# Multimodal_v4.net
KiCad netlist of a schematic drawn in EAGLE
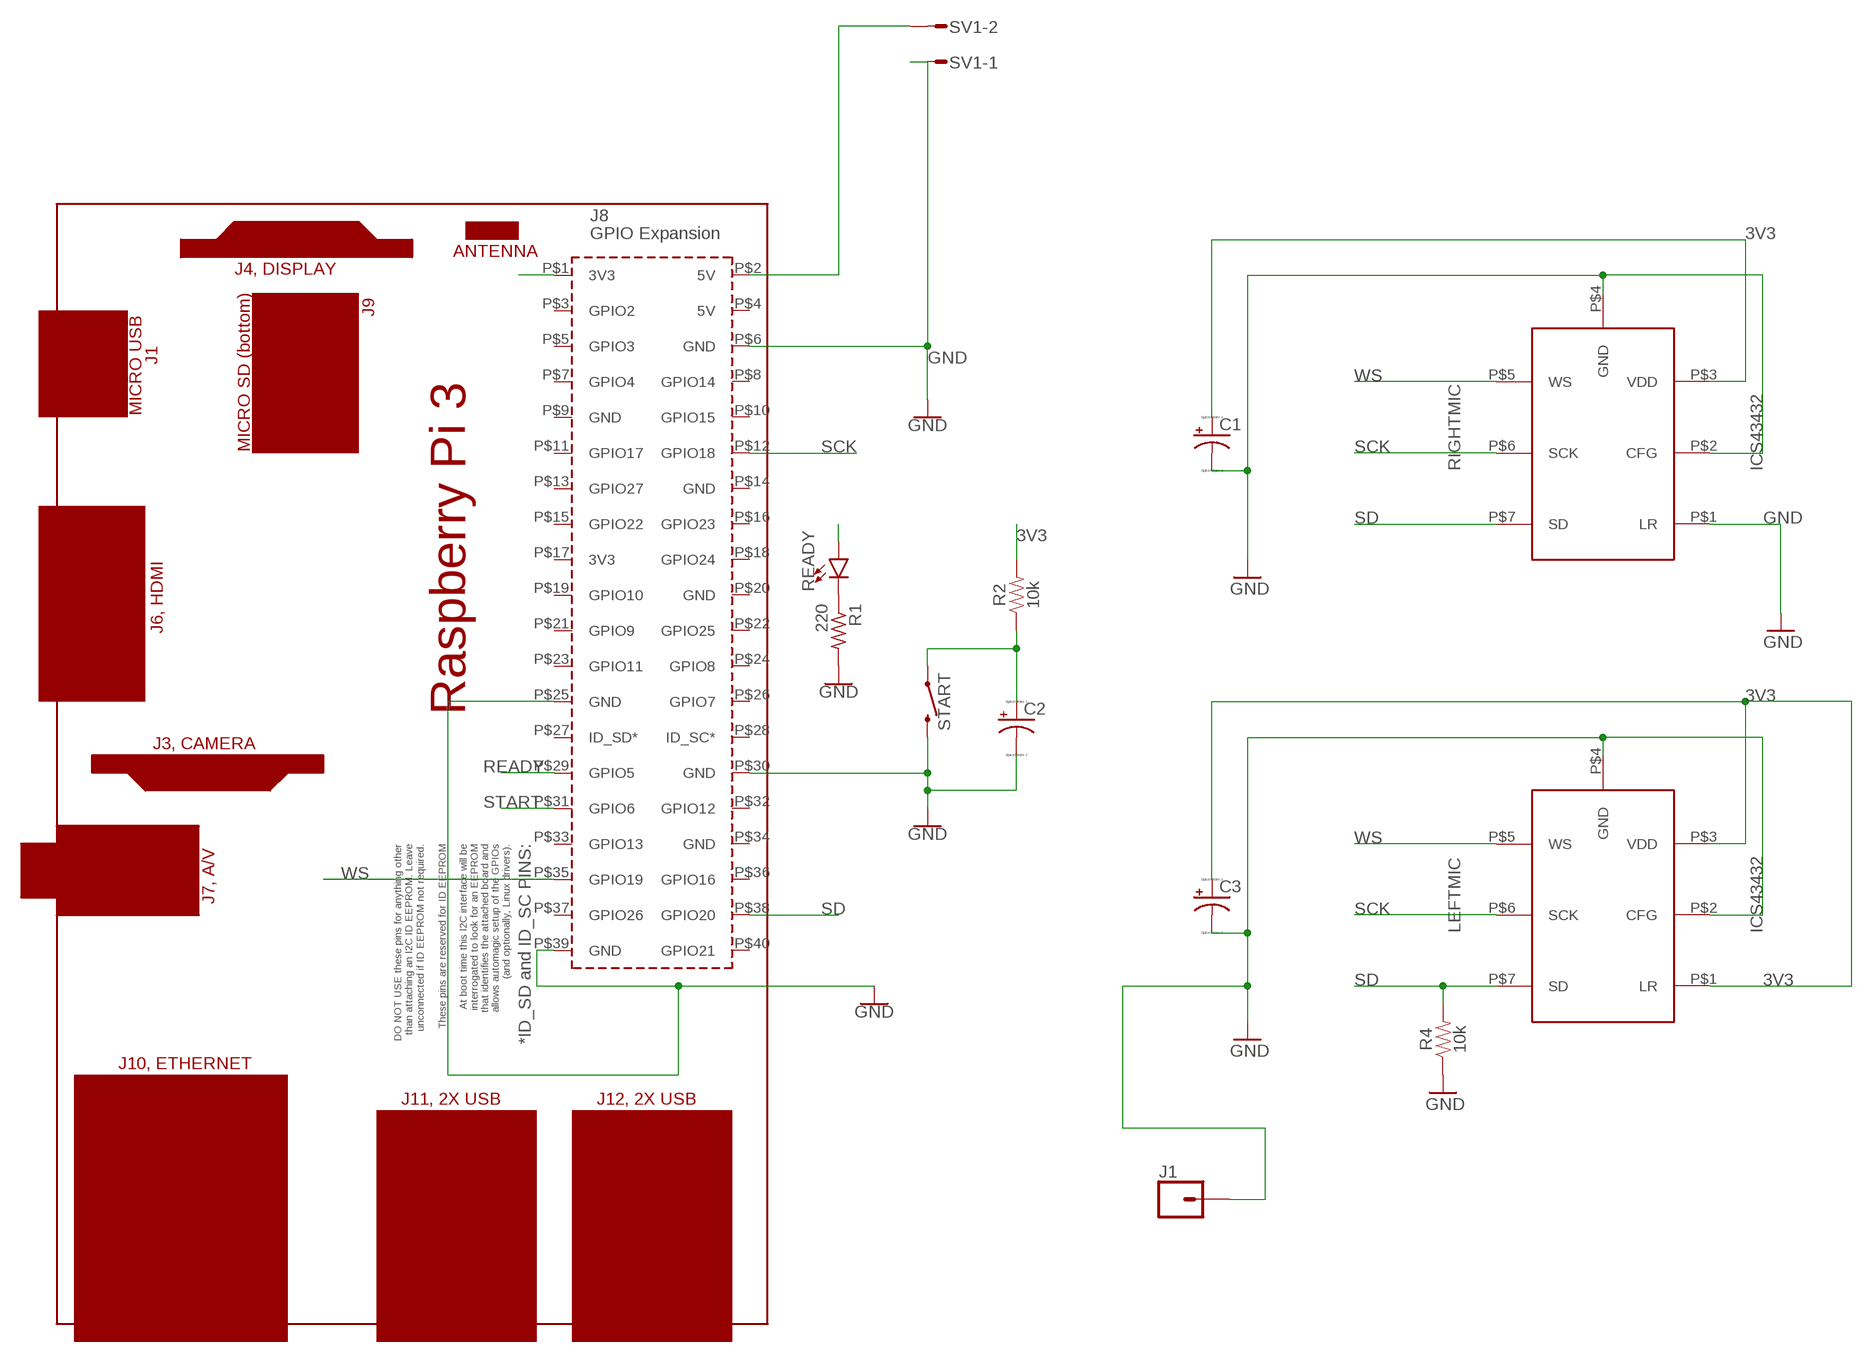
[diagram p0: schematic, sheet 1]

(export (version "E")
  (design (tool "Eeschema 10.0.6"))
  (components
    (comp (ref "C1")
      (value "CPOL-USE2.5-5")
      (footprint "eagle-import:E2,5-5")
      (libsource (lib "eagle-import") (part "CPOL-USE2.5-5"))
    )
    (comp (ref "C2")
      (value "CPOL-USE2.5-5")
      (footprint "eagle-import:E2,5-5")
      (libsource (lib "eagle-import") (part "CPOL-USE2.5-5"))
    )
    (comp (ref "C3")
      (value "CPOL-USE2.5-5")
      (footprint "eagle-import:E2,5-5")
      (libsource (lib "eagle-import") (part "CPOL-USE2.5-5"))
    )
    (comp (ref "J1")
      (value "CONN_01")
      (footprint "eagle-import:1X01")
      (libsource (lib "eagle-import") (part "CONN_01"))
    )
    (comp (ref "LEFTMIC")
      (value "ICS43432")
      (footprint "eagle-import:ICS43432")
      (libsource (lib "eagle-import") (part "ICS43432"))
    )
    (comp (ref "PCB1")
      (value "RPI3_40_PIN")
      (footprint "eagle-import:40_PIN")
      (libsource (lib "eagle-import") (part "RPI3_40_PIN"))
    )
    (comp (ref "R1")
      (value "220")
      (footprint "eagle-import:0207_7")
      (libsource (lib "eagle-import") (part "R-US_0207/7"))
    )
    (comp (ref "R2")
      (value "10k")
      (footprint "eagle-import:AXIAL-0.3-KIT")
      (libsource (lib "eagle-import") (part "10KOHM-HORIZ_KIT-1/4W-5%"))
    )
    (comp (ref "R4")
      (value "10k")
      (footprint "eagle-import:AXIAL-0.3-KIT")
      (libsource (lib "eagle-import") (part "10KOHM-HORIZ_KIT-1/4W-5%"))
    )
    (comp (ref "READY")
      (value "LED3MM")
      (footprint "eagle-import:LED_3MM")
      (libsource (lib "eagle-import") (part "LED3MM"))
    )
    (comp (ref "RIGHTMIC")
      (value "ICS43432")
      (footprint "eagle-import:ICS43432")
      (libsource (lib "eagle-import") (part "ICS43432"))
    )
    (comp (ref "START")
      (value "MOMENTARY-SWITCH-SPST-PTH-6.0MM")
      (footprint "eagle-import:TACTILE_SWITCH_PTH_6.0MM")
      (libsource (lib "eagle-import") (part "MOMENTARY-SWITCH-SPST-PTH-6.0MM"))
    )
    (comp (ref "SV1")
      (value "L02P")
      (footprint "eagle-import:L02P")
      (libsource (lib "eagle-import") (part "L02P"))
    )
  )
  (nets
    (net (code "1") (name "/3V3") (class "Default")
      (node (ref "C1") (pin "+") (pinfunction "+_+") (pintype "passive"))
      (node (ref "C3") (pin "+") (pinfunction "+_+") (pintype "passive"))
      (node (ref "LEFTMIC") (pin "P$1") (pinfunction "LR_P$1") (pintype "bidirectional"))
      (node (ref "LEFTMIC") (pin "P$3") (pinfunction "VDD_P$3") (pintype "bidirectional"))
      (node (ref "PCB1") (pin "P$1") (pinfunction "3V3_P$1") (pintype "bidirectional"))
      (node (ref "R2") (pin "P$2") (pinfunction "2_P$2") (pintype "passive"))
      (node (ref "RIGHTMIC") (pin "P$3") (pinfunction "VDD_P$3") (pintype "bidirectional"))
    )
    (net (code "2") (name "/READY") (class "Default")
      (node (ref "PCB1") (pin "P$29") (pinfunction "GPIO5_P$29") (pintype "bidirectional"))
      (node (ref "READY") (pin "A") (pinfunction "A_A") (pintype "passive"))
    )
    (net (code "3") (name "/SCK") (class "Default")
      (node (ref "LEFTMIC") (pin "P$6") (pinfunction "SCK_P$6") (pintype "bidirectional"))
      (node (ref "PCB1") (pin "P$12") (pinfunction "GPIO18_P$12") (pintype "bidirectional"))
      (node (ref "RIGHTMIC") (pin "P$6") (pinfunction "SCK_P$6") (pintype "bidirectional"))
    )
    (net (code "4") (name "/SD") (class "Default")
      (node (ref "LEFTMIC") (pin "P$7") (pinfunction "SD_P$7") (pintype "bidirectional"))
      (node (ref "PCB1") (pin "P$38") (pinfunction "GPIO20_P$38") (pintype "bidirectional"))
      (node (ref "R4") (pin "P$2") (pinfunction "2_P$2") (pintype "passive"))
      (node (ref "RIGHTMIC") (pin "P$7") (pinfunction "SD_P$7") (pintype "bidirectional"))
    )
    (net (code "5") (name "/START") (class "Default")
      (node (ref "C2") (pin "+") (pinfunction "+_+") (pintype "passive"))
      (node (ref "PCB1") (pin "P$31") (pinfunction "GPIO6_P$31") (pintype "bidirectional"))
      (node (ref "R2") (pin "P$1") (pinfunction "1_P$1") (pintype "passive"))
      (node (ref "START") (pin "1") (pinfunction "1_1") (pintype "passive"))
    )
    (net (code "6") (name "/WS") (class "Default")
      (node (ref "LEFTMIC") (pin "P$5") (pinfunction "WS_P$5") (pintype "bidirectional"))
      (node (ref "PCB1") (pin "P$35") (pinfunction "GPIO19_P$35") (pintype "bidirectional"))
      (node (ref "RIGHTMIC") (pin "P$5") (pinfunction "WS_P$5") (pintype "bidirectional"))
    )
    (net (code "7") (name "GND") (class "Default")
      (node (ref "C1") (pin "-") (pinfunction "-_-") (pintype "passive"))
      (node (ref "C2") (pin "-") (pinfunction "-_-") (pintype "passive"))
      (node (ref "C3") (pin "-") (pinfunction "-_-") (pintype "passive"))
      (node (ref "J1") (pin "1") (pinfunction "1_1") (pintype "passive"))
      (node (ref "LEFTMIC") (pin "P$2") (pinfunction "CFG_P$2") (pintype "bidirectional"))
      (node (ref "LEFTMIC") (pin "P$4") (pinfunction "GND_P$4") (pintype "bidirectional"))
      (node (ref "PCB1") (pin "P$25") (pinfunction "GND_P$25") (pintype "bidirectional"))
      (node (ref "PCB1") (pin "P$30") (pinfunction "GND_P$30") (pintype "bidirectional"))
      (node (ref "PCB1") (pin "P$39") (pinfunction "GND_P$39") (pintype "bidirectional"))
      (node (ref "PCB1") (pin "P$6") (pinfunction "GND_P$6") (pintype "bidirectional"))
      (node (ref "R1") (pin "2") (pinfunction "2_2") (pintype "passive"))
      (node (ref "R4") (pin "P$1") (pinfunction "1_P$1") (pintype "passive"))
      (node (ref "RIGHTMIC") (pin "P$1") (pinfunction "LR_P$1") (pintype "bidirectional"))
      (node (ref "RIGHTMIC") (pin "P$2") (pinfunction "CFG_P$2") (pintype "bidirectional"))
      (node (ref "RIGHTMIC") (pin "P$4") (pinfunction "GND_P$4") (pintype "bidirectional"))
      (node (ref "START") (pin "3") (pinfunction "2_3") (pintype "passive"))
      (node (ref "SV1") (pin "1") (pinfunction "S_1") (pintype "passive"))
    )
    (net (code "8") (name "Net-(READY-C)") (class "Default")
      (node (ref "R1") (pin "1") (pinfunction "1_1") (pintype "passive"))
      (node (ref "READY") (pin "K") (pinfunction "C_K") (pintype "passive"))
    )
    (net (code "9") (name "Net-(SV1B-S)") (class "Default")
      (node (ref "PCB1") (pin "P$2") (pinfunction "5V_P$2") (pintype "bidirectional"))
      (node (ref "SV1") (pin "2") (pinfunction "S_2") (pintype "passive"))
    )
    (net (code "10") (name "unconnected-(PCB1-3V3-PadP$17)") (class "Default")
      (node (ref "PCB1") (pin "P$17") (pinfunction "3V3_P$17") (pintype "bidirectional"))
    )
    (net (code "11") (name "unconnected-(PCB1-5V-PadP$4)") (class "Default")
      (node (ref "PCB1") (pin "P$4") (pinfunction "5V_P$4") (pintype "bidirectional"))
    )
    (net (code "12") (name "unconnected-(PCB1-GND-PadP$9)") (class "Default")
      (node (ref "PCB1") (pin "P$9") (pinfunction "GND_P$9") (pintype "bidirectional"))
    )
    (net (code "13") (name "unconnected-(PCB1-GND-PadP$14)") (class "Default")
      (node (ref "PCB1") (pin "P$14") (pinfunction "GND_P$14") (pintype "bidirectional"))
    )
    (net (code "14") (name "unconnected-(PCB1-GND-PadP$20)") (class "Default")
      (node (ref "PCB1") (pin "P$20") (pinfunction "GND_P$20") (pintype "bidirectional"))
    )
    (net (code "15") (name "unconnected-(PCB1-GND-PadP$34)") (class "Default")
      (node (ref "PCB1") (pin "P$34") (pinfunction "GND_P$34") (pintype "bidirectional"))
    )
    (net (code "16") (name "unconnected-(PCB1-GPIO2-PadP$3)") (class "Default")
      (node (ref "PCB1") (pin "P$3") (pinfunction "GPIO2_P$3") (pintype "bidirectional"))
    )
    (net (code "17") (name "unconnected-(PCB1-GPIO3-PadP$5)") (class "Default")
      (node (ref "PCB1") (pin "P$5") (pinfunction "GPIO3_P$5") (pintype "bidirectional"))
    )
    (net (code "18") (name "unconnected-(PCB1-GPIO4-PadP$7)") (class "Default")
      (node (ref "PCB1") (pin "P$7") (pinfunction "GPIO4_P$7") (pintype "bidirectional"))
    )
    (net (code "19") (name "unconnected-(PCB1-GPIO7-PadP$26)") (class "Default")
      (node (ref "PCB1") (pin "P$26") (pinfunction "GPIO7_P$26") (pintype "bidirectional"))
    )
    (net (code "20") (name "unconnected-(PCB1-GPIO8-PadP$24)") (class "Default")
      (node (ref "PCB1") (pin "P$24") (pinfunction "GPIO8_P$24") (pintype "bidirectional"))
    )
    (net (code "21") (name "unconnected-(PCB1-GPIO9-PadP$21)") (class "Default")
      (node (ref "PCB1") (pin "P$21") (pinfunction "GPIO9_P$21") (pintype "bidirectional"))
    )
    (net (code "22") (name "unconnected-(PCB1-GPIO10-PadP$19)") (class "Default")
      (node (ref "PCB1") (pin "P$19") (pinfunction "GPIO10_P$19") (pintype "bidirectional"))
    )
    (net (code "23") (name "unconnected-(PCB1-GPIO11-PadP$23)") (class "Default")
      (node (ref "PCB1") (pin "P$23") (pinfunction "GPIO11_P$23") (pintype "bidirectional"))
    )
    (net (code "24") (name "unconnected-(PCB1-GPIO12-PadP$32)") (class "Default")
      (node (ref "PCB1") (pin "P$32") (pinfunction "GPIO12_P$32") (pintype "bidirectional"))
    )
    (net (code "25") (name "unconnected-(PCB1-GPIO13-PadP$33)") (class "Default")
      (node (ref "PCB1") (pin "P$33") (pinfunction "GPIO13_P$33") (pintype "bidirectional"))
    )
    (net (code "26") (name "unconnected-(PCB1-GPIO14-PadP$8)") (class "Default")
      (node (ref "PCB1") (pin "P$8") (pinfunction "GPIO14_P$8") (pintype "bidirectional"))
    )
    (net (code "27") (name "unconnected-(PCB1-GPIO15-PadP$10)") (class "Default")
      (node (ref "PCB1") (pin "P$10") (pinfunction "GPIO15_P$10") (pintype "bidirectional"))
    )
    (net (code "28") (name "unconnected-(PCB1-GPIO16-PadP$36)") (class "Default")
      (node (ref "PCB1") (pin "P$36") (pinfunction "GPIO16_P$36") (pintype "bidirectional"))
    )
    (net (code "29") (name "unconnected-(PCB1-GPIO17-PadP$11)") (class "Default")
      (node (ref "PCB1") (pin "P$11") (pinfunction "GPIO17_P$11") (pintype "bidirectional"))
    )
    (net (code "30") (name "unconnected-(PCB1-GPIO21-PadP$40)") (class "Default")
      (node (ref "PCB1") (pin "P$40") (pinfunction "GPIO21_P$40") (pintype "bidirectional"))
    )
    (net (code "31") (name "unconnected-(PCB1-GPIO22-PadP$15)") (class "Default")
      (node (ref "PCB1") (pin "P$15") (pinfunction "GPIO22_P$15") (pintype "bidirectional"))
    )
    (net (code "32") (name "unconnected-(PCB1-GPIO23-PadP$16)") (class "Default")
      (node (ref "PCB1") (pin "P$16") (pinfunction "GPIO23_P$16") (pintype "bidirectional"))
    )
    (net (code "33") (name "unconnected-(PCB1-GPIO24-PadP$18)") (class "Default")
      (node (ref "PCB1") (pin "P$18") (pinfunction "GPIO24_P$18") (pintype "bidirectional"))
    )
    (net (code "34") (name "unconnected-(PCB1-GPIO25-PadP$22)") (class "Default")
      (node (ref "PCB1") (pin "P$22") (pinfunction "GPIO25_P$22") (pintype "bidirectional"))
    )
    (net (code "35") (name "unconnected-(PCB1-GPIO26-PadP$37)") (class "Default")
      (node (ref "PCB1") (pin "P$37") (pinfunction "GPIO26_P$37") (pintype "bidirectional"))
    )
    (net (code "36") (name "unconnected-(PCB1-GPIO27-PadP$13)") (class "Default")
      (node (ref "PCB1") (pin "P$13") (pinfunction "GPIO27_P$13") (pintype "bidirectional"))
    )
    (net (code "37") (name "unconnected-(PCB1-ID_SC*-PadP$28)") (class "Default")
      (node (ref "PCB1") (pin "P$28") (pinfunction "ID_SC*_P$28") (pintype "bidirectional"))
    )
    (net (code "38") (name "unconnected-(PCB1-ID_SD*-PadP$27)") (class "Default")
      (node (ref "PCB1") (pin "P$27") (pinfunction "ID_SD*_P$27") (pintype "bidirectional"))
    )
  )
)
